# Filter.net
KiCad netlist of a schematic drawn in Altium Designer
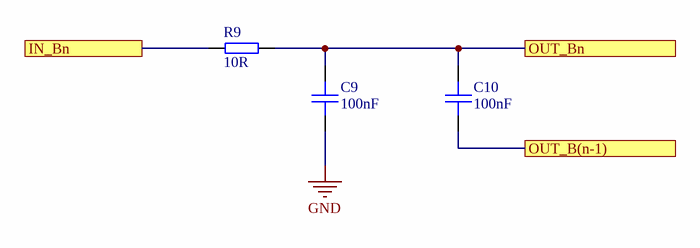
[diagram p0: Filter.SchDoc]

(export (version "E")
  (design (tool "Eeschema 10.0.6"))
  (components
    (comp (ref "C9")
      (value "100nF")
      (footprint "CAP 0603")
      (libsource (lib "SVNDatabase") (part "Capacitor"))
    )
    (comp (ref "C10")
      (value "100nF")
      (footprint "CAP 0603")
      (libsource (lib "SVNDatabase") (part "Capacitor"))
    )
    (comp (ref "R9")
      (value "10R")
      (footprint "0603")
      (fields (field (name "TOLERANCE") "1%"))
      (libsource (lib "SVNDatabase") (part "R"))
    )
  )
  (nets
    (net (code "1") (name "/IN_Bn") (class "Default")
      (node (ref "R9") (pin "1") (pinfunction "1_1") (pintype "passive"))
    )
    (net (code "2") (name "/OUT_B(n-1)") (class "Default")
      (node (ref "C10") (pin "1") (pinfunction "1_1") (pintype "passive"))
    )
    (net (code "3") (name "/OUT_Bn") (class "Default")
      (node (ref "C10") (pin "2") (pinfunction "2_2") (pintype "passive"))
      (node (ref "C9") (pin "2") (pinfunction "2_2") (pintype "passive"))
      (node (ref "R9") (pin "2") (pinfunction "2_2") (pintype "passive"))
    )
    (net (code "4") (name "GND") (class "Default")
      (node (ref "C9") (pin "1") (pinfunction "1_1") (pintype "passive"))
    )
  )
)
